# MCU.net
KiCad netlist of a schematic drawn in Altium Designer
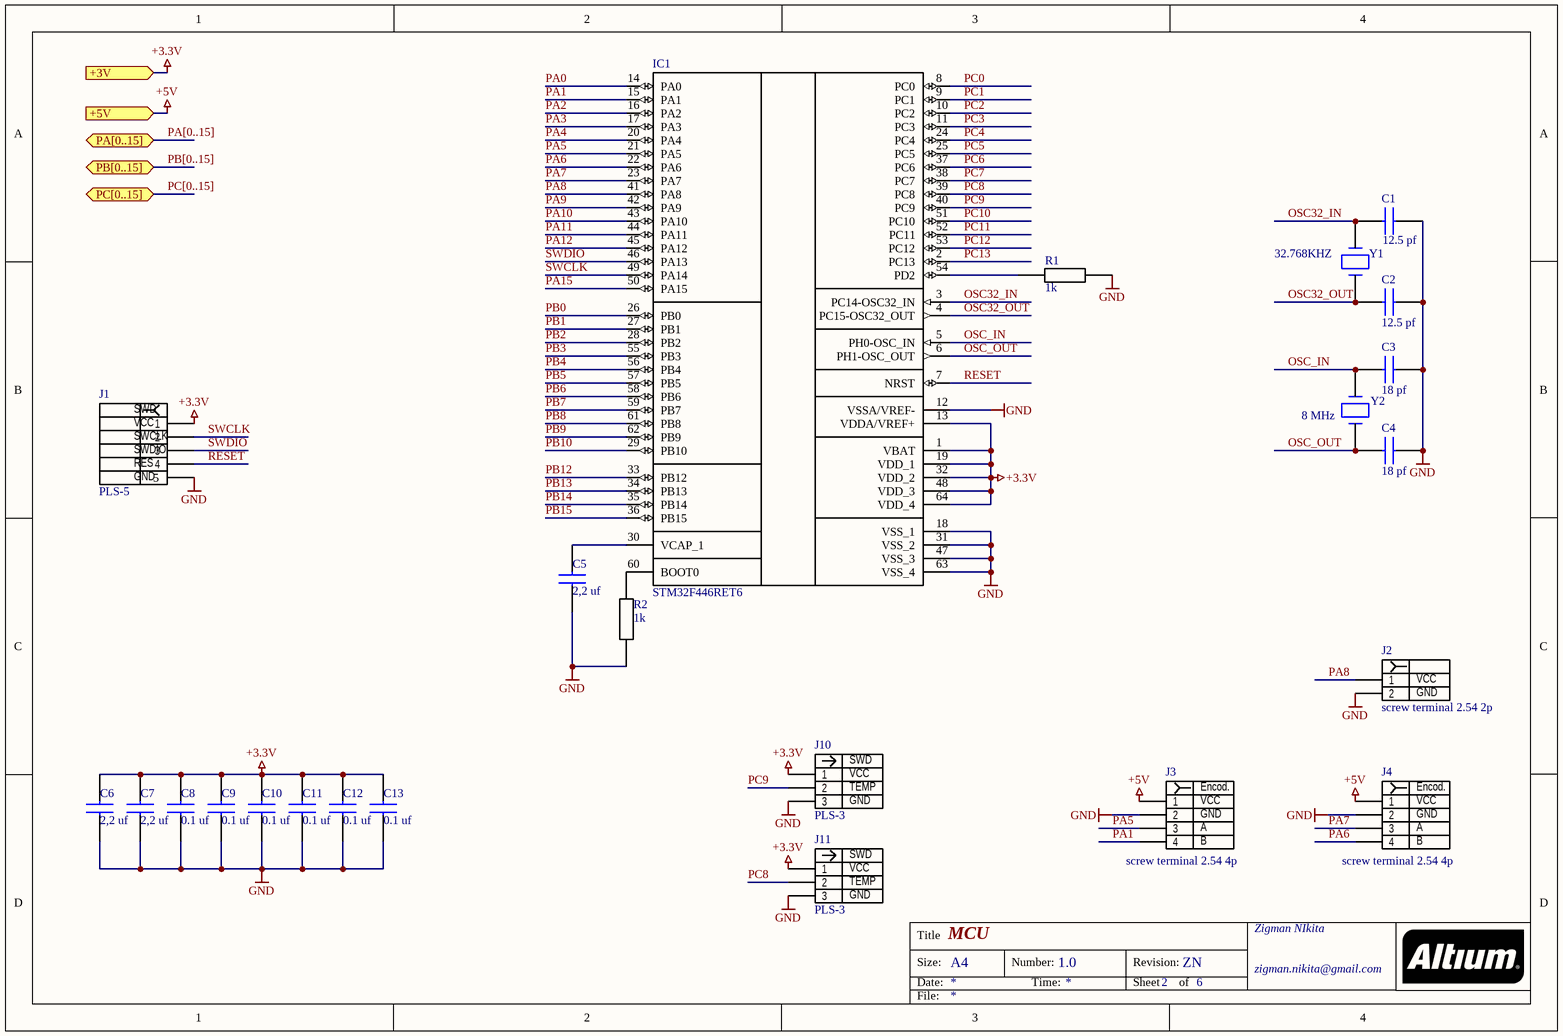
[diagram p0: MCU.SchDoc]

(export (version "E")
  (design (tool "Eeschema 10.0.6"))
  (components
    (comp (ref "C1")
      (value "12.5 pf")
      (footprint "SamacSys:CAPC1608X90N")
      (description "AVX 18pF 200V dc 0603")
      (libsource (lib "RobotLib") (part "0603"))
    )
    (comp (ref "C2")
      (value "12.5 pf")
      (footprint "SamacSys:CAPC1608X90N")
      (description "AVX 18pF 200V dc 0603")
      (libsource (lib "RobotLib") (part "0603"))
    )
    (comp (ref "C3")
      (value "18 pf")
      (footprint "SamacSys:CAPC1608X90N")
      (description "AVX 18pF 200V dc 0603")
      (libsource (lib "RobotLib") (part "0603"))
    )
    (comp (ref "C4")
      (value "18 pf")
      (footprint "SamacSys:CAPC1608X90N")
      (description "AVX 18pF 200V dc 0603")
      (libsource (lib "RobotLib") (part "0603"))
    )
    (comp (ref "C5")
      (value "2,2 uf")
      (footprint "SamacSys:CAPC1608X90N")
      (description "Murata 2.2 uF X7R 10% 10V dc 0603")
      (fields (field (name "MANUFACTURER_PART_NUMBER") "06033C393JAT2A"))
      (libsource (lib "RobotLib") (part "0603"))
    )
    (comp (ref "C6")
      (value "2,2 uf")
      (footprint "SamacSys:CAPC1608X90N")
      (description "Murata 2.2 uF X7R 10% 10V dc 0603")
      (fields (field (name "MANUFACTURER_PART_NUMBER") "06033C393JAT2A"))
      (libsource (lib "RobotLib") (part "0603"))
    )
    (comp (ref "C7")
      (value "2,2 uf")
      (footprint "SamacSys:CAPC1608X90N")
      (description "Murata 2.2 uF X7R 10% 10V dc 0603")
      (fields (field (name "MANUFACTURER_PART_NUMBER") "06033C393JAT2A"))
      (libsource (lib "RobotLib") (part "0603"))
    )
    (comp (ref "C8")
      (value "0.1 uf")
      (footprint "SamacSys:CAPC1608X90N")
      (description "AVX 0.1 uF 16v dc 0603")
      (libsource (lib "RobotLib") (part "0603"))
    )
    (comp (ref "C9")
      (value "0.1 uf")
      (footprint "SamacSys:CAPC1608X90N")
      (description "AVX 0.1 uF 16v dc 0603")
      (libsource (lib "RobotLib") (part "0603"))
    )
    (comp (ref "C10")
      (value "0.1 uf")
      (footprint "SamacSys:CAPC1608X90N")
      (description "AVX 0.1 uF 16v dc 0603")
      (libsource (lib "RobotLib") (part "0603"))
    )
    (comp (ref "C11")
      (value "0.1 uf")
      (footprint "SamacSys:CAPC1608X90N")
      (description "AVX 0.1 uF 16v dc 0603")
      (libsource (lib "RobotLib") (part "0603"))
    )
    (comp (ref "C12")
      (value "0.1 uf")
      (footprint "SamacSys:CAPC1608X90N")
      (description "AVX 0.1 uF 16v dc 0603")
      (libsource (lib "RobotLib") (part "0603"))
    )
    (comp (ref "C13")
      (value "0.1 uf")
      (footprint "SamacSys:CAPC1608X90N")
      (description "AVX 0.1 uF 16v dc 0603")
      (libsource (lib "RobotLib") (part "0603"))
    )
    (comp (ref "IC1")
      (value "STM32F446RET6")
      (footprint "QFP50P1200X1200X160-64N")
      (description "Integrated Circuit")
      (fields (field (name "MOUSER PART NUMBER") "511-STM32F446RET6"))
      (libsource (lib "RobotLib") (part "STM32F446RET6"))
    )
    (comp (ref "J1")
      (value "PLS-5")
      (footprint "TE_826646-5")
      (description "Board-To-Board Connector, Through Hole, Header, 5, 2.54 mm, Gold Plated Contacts")
      (fields (field (name "MF") "TE Connectivity") (field (name "MP") "826646-5"))
      (libsource (lib "RobotLib") (part "PLS-5"))
    )
    (comp (ref "J2")
      (value "screw terminal 2.54 2p")
      (footprint "1725672-2-2.54")
      (description "Connector")
      (fields
        (field (name "MANUFACTURER_PART_NUMBER") "1725672")
        (field (name "MOUSER PART NUMBER") "651-1725672")
      )
      (libsource (lib "RobotLib") (part "screw terminal 2.54 2p"))
    )
    (comp (ref "J3")
      (value "screw terminal 2.54 4p")
      (footprint "1725672-4-2.54")
      (description "Connector")
      (fields
        (field (name "MANUFACTURER_PART_NUMBER") "1725672")
        (field (name "MOUSER PART NUMBER") "651-1725672")
      )
      (libsource (lib "RobotLib") (part "screw terminal 2.54 4p"))
    )
    (comp (ref "J4")
      (value "screw terminal 2.54 4p")
      (footprint "1725672-4-2.54")
      (description "Connector")
      (fields
        (field (name "MANUFACTURER_PART_NUMBER") "1725672")
        (field (name "MOUSER PART NUMBER") "651-1725672")
      )
      (libsource (lib "RobotLib") (part "screw terminal 2.54 4p"))
    )
    (comp (ref "J10")
      (value "PLS-3")
      (footprint "TE_826646-3")
      (description "Board-To-Board Connector, Through Hole, Header, 5, 2.54 mm, Gold Plated Contacts")
      (fields (field (name "MF") "TE Connectivity") (field (name "MP") "826646-5"))
      (libsource (lib "RobotLib") (part "PLS-3"))
    )
    (comp (ref "J11")
      (value "PLS-3")
      (footprint "TE_826646-3")
      (description "Board-To-Board Connector, Through Hole, Header, 5, 2.54 mm, Gold Plated Contacts")
      (fields (field (name "MF") "TE Connectivity") (field (name "MP") "826646-5"))
      (libsource (lib "RobotLib") (part "PLS-3"))
    )
    (comp (ref "R1")
      (value "1k")
      (footprint "SamacSys:RESC1608X55N")
      (description "RS PRO SMD-Widerstand, 1kΩ ±5%")
      (libsource (lib "") (part "res 0603_1"))
    )
    (comp (ref "R2")
      (value "1k")
      (footprint "SamacSys:RESC1608X55N")
      (description "RS PRO SMD-Widerstand, 1kΩ ±5%")
      (libsource (lib "RobotLib") (part "res 0603"))
    )
    (comp (ref "Y1")
      (value "32.768KHZ")
      (footprint "SamacSys:9HT1132768KDZBT")
      (description "Quarz CM7V-T1A 32.768KHZ 7PF +/-20PPM TB QA 32.768kHz, ±20ppm")
      (fields (field (name "MANUFACTURER_PART_NUMBER") "CM7V-T1A"))
      (libsource (lib "RobotLib") (part "CM7V-T1A 32.768KHZ"))
    )
    (comp (ref "Y2")
      (value "8 MHz")
      (footprint "ABM2")
      (description "Quarz ABM2-8.000MHZ-D4Y-T 8MHz, ±30ppm")
      (fields (field (name "MANUFACTURER_PART_NUMBER") "ABM2-8.000MHZ-D4Y-T"))
      (libsource (lib "RobotLib") (part "ABM2-8.000MHZ-D4Y-T"))
    )
  )
  (nets
    (net (code "6") (name "+3.3V") (class "Default")
      (node (ref "C10") (pin "2") (pinfunction "2_2") (pintype "passive"))
      (node (ref "C11") (pin "2") (pinfunction "2_2") (pintype "passive"))
      (node (ref "C12") (pin "2") (pinfunction "2_2") (pintype "passive"))
      (node (ref "C13") (pin "2") (pinfunction "2_2") (pintype "passive"))
      (node (ref "C6") (pin "2") (pinfunction "2_2") (pintype "passive"))
      (node (ref "C7") (pin "2") (pinfunction "2_2") (pintype "passive"))
      (node (ref "C8") (pin "2") (pinfunction "2_2") (pintype "passive"))
      (node (ref "C9") (pin "2") (pinfunction "2_2") (pintype "passive"))
      (node (ref "IC1") (pin "1") (pinfunction "VBAT_1") (pintype "power_in"))
      (node (ref "IC1") (pin "13") (pinfunction "VDDA/VREF+_13") (pintype "power_in"))
      (node (ref "IC1") (pin "19") (pinfunction "VDD_1_19") (pintype "power_in"))
      (node (ref "IC1") (pin "32") (pinfunction "VDD_2_32") (pintype "power_in"))
      (node (ref "IC1") (pin "48") (pinfunction "VDD_3_48") (pintype "power_in"))
      (node (ref "IC1") (pin "64") (pinfunction "VDD_4_64") (pintype "power_in"))
      (node (ref "J1") (pin "1") (pinfunction "1_1") (pintype "passive"))
      (node (ref "J10") (pin "1") (pinfunction "1_1") (pintype "passive"))
      (node (ref "J11") (pin "1") (pinfunction "1_1") (pintype "passive"))
    )
    (net (code "7") (name "+5V") (class "Default")
      (node (ref "J3") (pin "1") (pinfunction "1_1") (pintype "passive"))
      (node (ref "J4") (pin "1") (pinfunction "1_1") (pintype "passive"))
    )
    (net (code "8") (name "/OSC32_IN") (class "Default")
      (node (ref "C1") (pin "2") (pinfunction "2_2") (pintype "passive"))
      (node (ref "IC1") (pin "3") (pinfunction "PC14-OSC32_IN_3") (pintype "input"))
      (node (ref "Y1") (pin "2") (pinfunction "2_2") (pintype "passive"))
    )
    (net (code "9") (name "/OSC32_OUT") (class "Default")
      (node (ref "C2") (pin "2") (pinfunction "2_2") (pintype "passive"))
      (node (ref "IC1") (pin "4") (pinfunction "PC15-OSC32_OUT_4") (pintype "output"))
      (node (ref "Y1") (pin "1") (pinfunction "1_1") (pintype "passive"))
    )
    (net (code "10") (name "/OSC_IN") (class "Default")
      (node (ref "C3") (pin "2") (pinfunction "2_2") (pintype "passive"))
      (node (ref "IC1") (pin "5") (pinfunction "PH0-OSC_IN_5") (pintype "input"))
      (node (ref "Y2") (pin "2") (pinfunction "2_2") (pintype "passive"))
    )
    (net (code "11") (name "/OSC_OUT") (class "Default")
      (node (ref "C4") (pin "2") (pinfunction "2_2") (pintype "passive"))
      (node (ref "IC1") (pin "6") (pinfunction "PH1-OSC_OUT_6") (pintype "output"))
      (node (ref "Y2") (pin "1") (pinfunction "1_1") (pintype "passive"))
    )
    (net (code "12") (name "/PA0") (class "Default")
      (node (ref "IC1") (pin "14") (pinfunction "PA0_14") (pintype "bidirectional"))
    )
    (net (code "13") (name "/PA1") (class "Default")
      (node (ref "IC1") (pin "15") (pinfunction "PA1_15") (pintype "bidirectional"))
      (node (ref "J3") (pin "4") (pinfunction "4_4") (pintype "passive"))
    )
    (net (code "14") (name "/PA2") (class "Default")
      (node (ref "IC1") (pin "16") (pinfunction "PA2_16") (pintype "bidirectional"))
    )
    (net (code "15") (name "/PA3") (class "Default")
      (node (ref "IC1") (pin "17") (pinfunction "PA3_17") (pintype "bidirectional"))
    )
    (net (code "16") (name "/PA4") (class "Default")
      (node (ref "IC1") (pin "20") (pinfunction "PA4_20") (pintype "bidirectional"))
    )
    (net (code "17") (name "/PA5") (class "Default")
      (node (ref "IC1") (pin "21") (pinfunction "PA5_21") (pintype "bidirectional"))
      (node (ref "J3") (pin "3") (pinfunction "3_3") (pintype "passive"))
    )
    (net (code "18") (name "/PA6") (class "Default")
      (node (ref "IC1") (pin "22") (pinfunction "PA6_22") (pintype "bidirectional"))
      (node (ref "J4") (pin "4") (pinfunction "4_4") (pintype "passive"))
    )
    (net (code "19") (name "/PA7") (class "Default")
      (node (ref "IC1") (pin "23") (pinfunction "PA7_23") (pintype "bidirectional"))
      (node (ref "J4") (pin "3") (pinfunction "3_3") (pintype "passive"))
    )
    (net (code "20") (name "/PA8") (class "Default")
      (node (ref "IC1") (pin "41") (pinfunction "PA8_41") (pintype "bidirectional"))
      (node (ref "J2") (pin "1") (pinfunction "1_1") (pintype "passive"))
    )
    (net (code "21") (name "/PA9") (class "Default")
      (node (ref "IC1") (pin "42") (pinfunction "PA9_42") (pintype "bidirectional"))
    )
    (net (code "22") (name "/PA10") (class "Default")
      (node (ref "IC1") (pin "43") (pinfunction "PA10_43") (pintype "bidirectional"))
    )
    (net (code "23") (name "/PA11") (class "Default")
      (node (ref "IC1") (pin "44") (pinfunction "PA11_44") (pintype "bidirectional"))
    )
    (net (code "24") (name "/PA12") (class "Default")
      (node (ref "IC1") (pin "45") (pinfunction "PA12_45") (pintype "bidirectional"))
    )
    (net (code "25") (name "/PA15") (class "Default")
      (node (ref "IC1") (pin "50") (pinfunction "PA15_50") (pintype "bidirectional"))
    )
    (net (code "27") (name "/PB0") (class "Default")
      (node (ref "IC1") (pin "26") (pinfunction "PB0_26") (pintype "bidirectional"))
    )
    (net (code "28") (name "/PB1") (class "Default")
      (node (ref "IC1") (pin "27") (pinfunction "PB1_27") (pintype "bidirectional"))
    )
    (net (code "29") (name "/PB2") (class "Default")
      (node (ref "IC1") (pin "28") (pinfunction "PB2_28") (pintype "bidirectional"))
    )
    (net (code "30") (name "/PB3") (class "Default")
      (node (ref "IC1") (pin "55") (pinfunction "PB3_55") (pintype "bidirectional"))
    )
    (net (code "31") (name "/PB4") (class "Default")
      (node (ref "IC1") (pin "56") (pinfunction "PB4_56") (pintype "bidirectional"))
    )
    (net (code "32") (name "/PB5") (class "Default")
      (node (ref "IC1") (pin "57") (pinfunction "PB5_57") (pintype "bidirectional"))
    )
    (net (code "33") (name "/PB6") (class "Default")
      (node (ref "IC1") (pin "58") (pinfunction "PB6_58") (pintype "bidirectional"))
    )
    (net (code "34") (name "/PB7") (class "Default")
      (node (ref "IC1") (pin "59") (pinfunction "PB7_59") (pintype "bidirectional"))
    )
    (net (code "35") (name "/PB8") (class "Default")
      (node (ref "IC1") (pin "61") (pinfunction "PB8_61") (pintype "bidirectional"))
    )
    (net (code "36") (name "/PB9") (class "Default")
      (node (ref "IC1") (pin "62") (pinfunction "PB9_62") (pintype "bidirectional"))
    )
    (net (code "37") (name "/PB10") (class "Default")
      (node (ref "IC1") (pin "29") (pinfunction "PB10_29") (pintype "bidirectional"))
    )
    (net (code "38") (name "/PB12") (class "Default")
      (node (ref "IC1") (pin "33") (pinfunction "PB12_33") (pintype "bidirectional"))
    )
    (net (code "39") (name "/PB13") (class "Default")
      (node (ref "IC1") (pin "34") (pinfunction "PB13_34") (pintype "bidirectional"))
    )
    (net (code "40") (name "/PB14") (class "Default")
      (node (ref "IC1") (pin "35") (pinfunction "PB14_35") (pintype "bidirectional"))
    )
    (net (code "41") (name "/PB15") (class "Default")
      (node (ref "IC1") (pin "36") (pinfunction "PB15_36") (pintype "bidirectional"))
    )
    (net (code "43") (name "/PC0") (class "Default")
      (node (ref "IC1") (pin "8") (pinfunction "PC0_8") (pintype "bidirectional"))
    )
    (net (code "44") (name "/PC1") (class "Default")
      (node (ref "IC1") (pin "9") (pinfunction "PC1_9") (pintype "bidirectional"))
    )
    (net (code "45") (name "/PC2") (class "Default")
      (node (ref "IC1") (pin "10") (pinfunction "PC2_10") (pintype "bidirectional"))
    )
    (net (code "46") (name "/PC3") (class "Default")
      (node (ref "IC1") (pin "11") (pinfunction "PC3_11") (pintype "bidirectional"))
    )
    (net (code "47") (name "/PC4") (class "Default")
      (node (ref "IC1") (pin "24") (pinfunction "PC4_24") (pintype "bidirectional"))
    )
    (net (code "48") (name "/PC5") (class "Default")
      (node (ref "IC1") (pin "25") (pinfunction "PC5_25") (pintype "bidirectional"))
    )
    (net (code "49") (name "/PC6") (class "Default")
      (node (ref "IC1") (pin "37") (pinfunction "PC6_37") (pintype "bidirectional"))
    )
    (net (code "50") (name "/PC7") (class "Default")
      (node (ref "IC1") (pin "38") (pinfunction "PC7_38") (pintype "bidirectional"))
    )
    (net (code "51") (name "/PC8") (class "Default")
      (node (ref "IC1") (pin "39") (pinfunction "PC8_39") (pintype "bidirectional"))
      (node (ref "J11") (pin "2") (pinfunction "2_2") (pintype "passive"))
    )
    (net (code "52") (name "/PC9") (class "Default")
      (node (ref "IC1") (pin "40") (pinfunction "PC9_40") (pintype "bidirectional"))
      (node (ref "J10") (pin "2") (pinfunction "2_2") (pintype "passive"))
    )
    (net (code "53") (name "/PC10") (class "Default")
      (node (ref "IC1") (pin "51") (pinfunction "PC10_51") (pintype "bidirectional"))
    )
    (net (code "54") (name "/PC11") (class "Default")
      (node (ref "IC1") (pin "52") (pinfunction "PC11_52") (pintype "bidirectional"))
    )
    (net (code "55") (name "/PC12") (class "Default")
      (node (ref "IC1") (pin "53") (pinfunction "PC12_53") (pintype "bidirectional"))
    )
    (net (code "56") (name "/PC13") (class "Default")
      (node (ref "IC1") (pin "2") (pinfunction "PC13_2") (pintype "bidirectional"))
    )
    (net (code "58") (name "/RESET") (class "Default")
      (node (ref "IC1") (pin "7") (pinfunction "NRST_7") (pintype "bidirectional"))
      (node (ref "J1") (pin "4") (pinfunction "4_4") (pintype "passive"))
    )
    (net (code "59") (name "/SWCLK") (class "Default")
      (node (ref "IC1") (pin "49") (pinfunction "PA14_49") (pintype "bidirectional"))
      (node (ref "J1") (pin "2") (pinfunction "2_2") (pintype "passive"))
    )
    (net (code "60") (name "/SWDIO") (class "Default")
      (node (ref "IC1") (pin "46") (pinfunction "PA13_46") (pintype "bidirectional"))
      (node (ref "J1") (pin "3") (pinfunction "3_3") (pintype "passive"))
    )
    (net (code "61") (name "GND") (class "Default")
      (node (ref "C1") (pin "1") (pinfunction "1_1") (pintype "passive"))
      (node (ref "C10") (pin "1") (pinfunction "1_1") (pintype "passive"))
      (node (ref "C11") (pin "1") (pinfunction "1_1") (pintype "passive"))
      (node (ref "C12") (pin "1") (pinfunction "1_1") (pintype "passive"))
      (node (ref "C13") (pin "1") (pinfunction "1_1") (pintype "passive"))
      (node (ref "C2") (pin "1") (pinfunction "1_1") (pintype "passive"))
      (node (ref "C3") (pin "1") (pinfunction "1_1") (pintype "passive"))
      (node (ref "C4") (pin "1") (pinfunction "1_1") (pintype "passive"))
      (node (ref "C5") (pin "1") (pinfunction "1_1") (pintype "passive"))
      (node (ref "C6") (pin "1") (pinfunction "1_1") (pintype "passive"))
      (node (ref "C7") (pin "1") (pinfunction "1_1") (pintype "passive"))
      (node (ref "C8") (pin "1") (pinfunction "1_1") (pintype "passive"))
      (node (ref "C9") (pin "1") (pinfunction "1_1") (pintype "passive"))
      (node (ref "IC1") (pin "12") (pinfunction "VSSA/VREF-_12") (pintype "power_in"))
      (node (ref "IC1") (pin "18") (pinfunction "VSS_1_18") (pintype "power_in"))
      (node (ref "IC1") (pin "31") (pinfunction "VSS_2_31") (pintype "power_in"))
      (node (ref "IC1") (pin "47") (pinfunction "VSS_3_47") (pintype "power_in"))
      (node (ref "IC1") (pin "63") (pinfunction "VSS_4_63") (pintype "power_in"))
      (node (ref "J1") (pin "5") (pinfunction "5_5") (pintype "passive"))
      (node (ref "J10") (pin "3") (pinfunction "3_3") (pintype "passive"))
      (node (ref "J11") (pin "3") (pinfunction "3_3") (pintype "passive"))
      (node (ref "J2") (pin "2") (pinfunction "2_2") (pintype "passive"))
      (node (ref "J3") (pin "2") (pinfunction "2_2") (pintype "passive"))
      (node (ref "J4") (pin "2") (pinfunction "2_2") (pintype "passive"))
      (node (ref "R1") (pin "1") (pinfunction "1_1") (pintype "passive"))
      (node (ref "R2") (pin "2") (pinfunction "2_2") (pintype "passive"))
    )
    (net (code "62") (name "Net-(IC1-BOOT0)") (class "Default")
      (node (ref "IC1") (pin "60") (pinfunction "BOOT0_60") (pintype "passive"))
      (node (ref "R2") (pin "1") (pinfunction "1_1") (pintype "passive"))
    )
    (net (code "63") (name "Net-(IC1-PD2)") (class "Default")
      (node (ref "IC1") (pin "54") (pinfunction "PD2_54") (pintype "bidirectional"))
      (node (ref "R1") (pin "2") (pinfunction "2_2") (pintype "passive"))
    )
    (net (code "64") (name "Net-(IC1-VCAP_1)") (class "Default")
      (node (ref "C5") (pin "2") (pinfunction "2_2") (pintype "passive"))
      (node (ref "IC1") (pin "30") (pinfunction "VCAP_1_30") (pintype "passive"))
    )
  )
)
